# Relay_Control.net
KiCad netlist of a schematic drawn in EAGLE
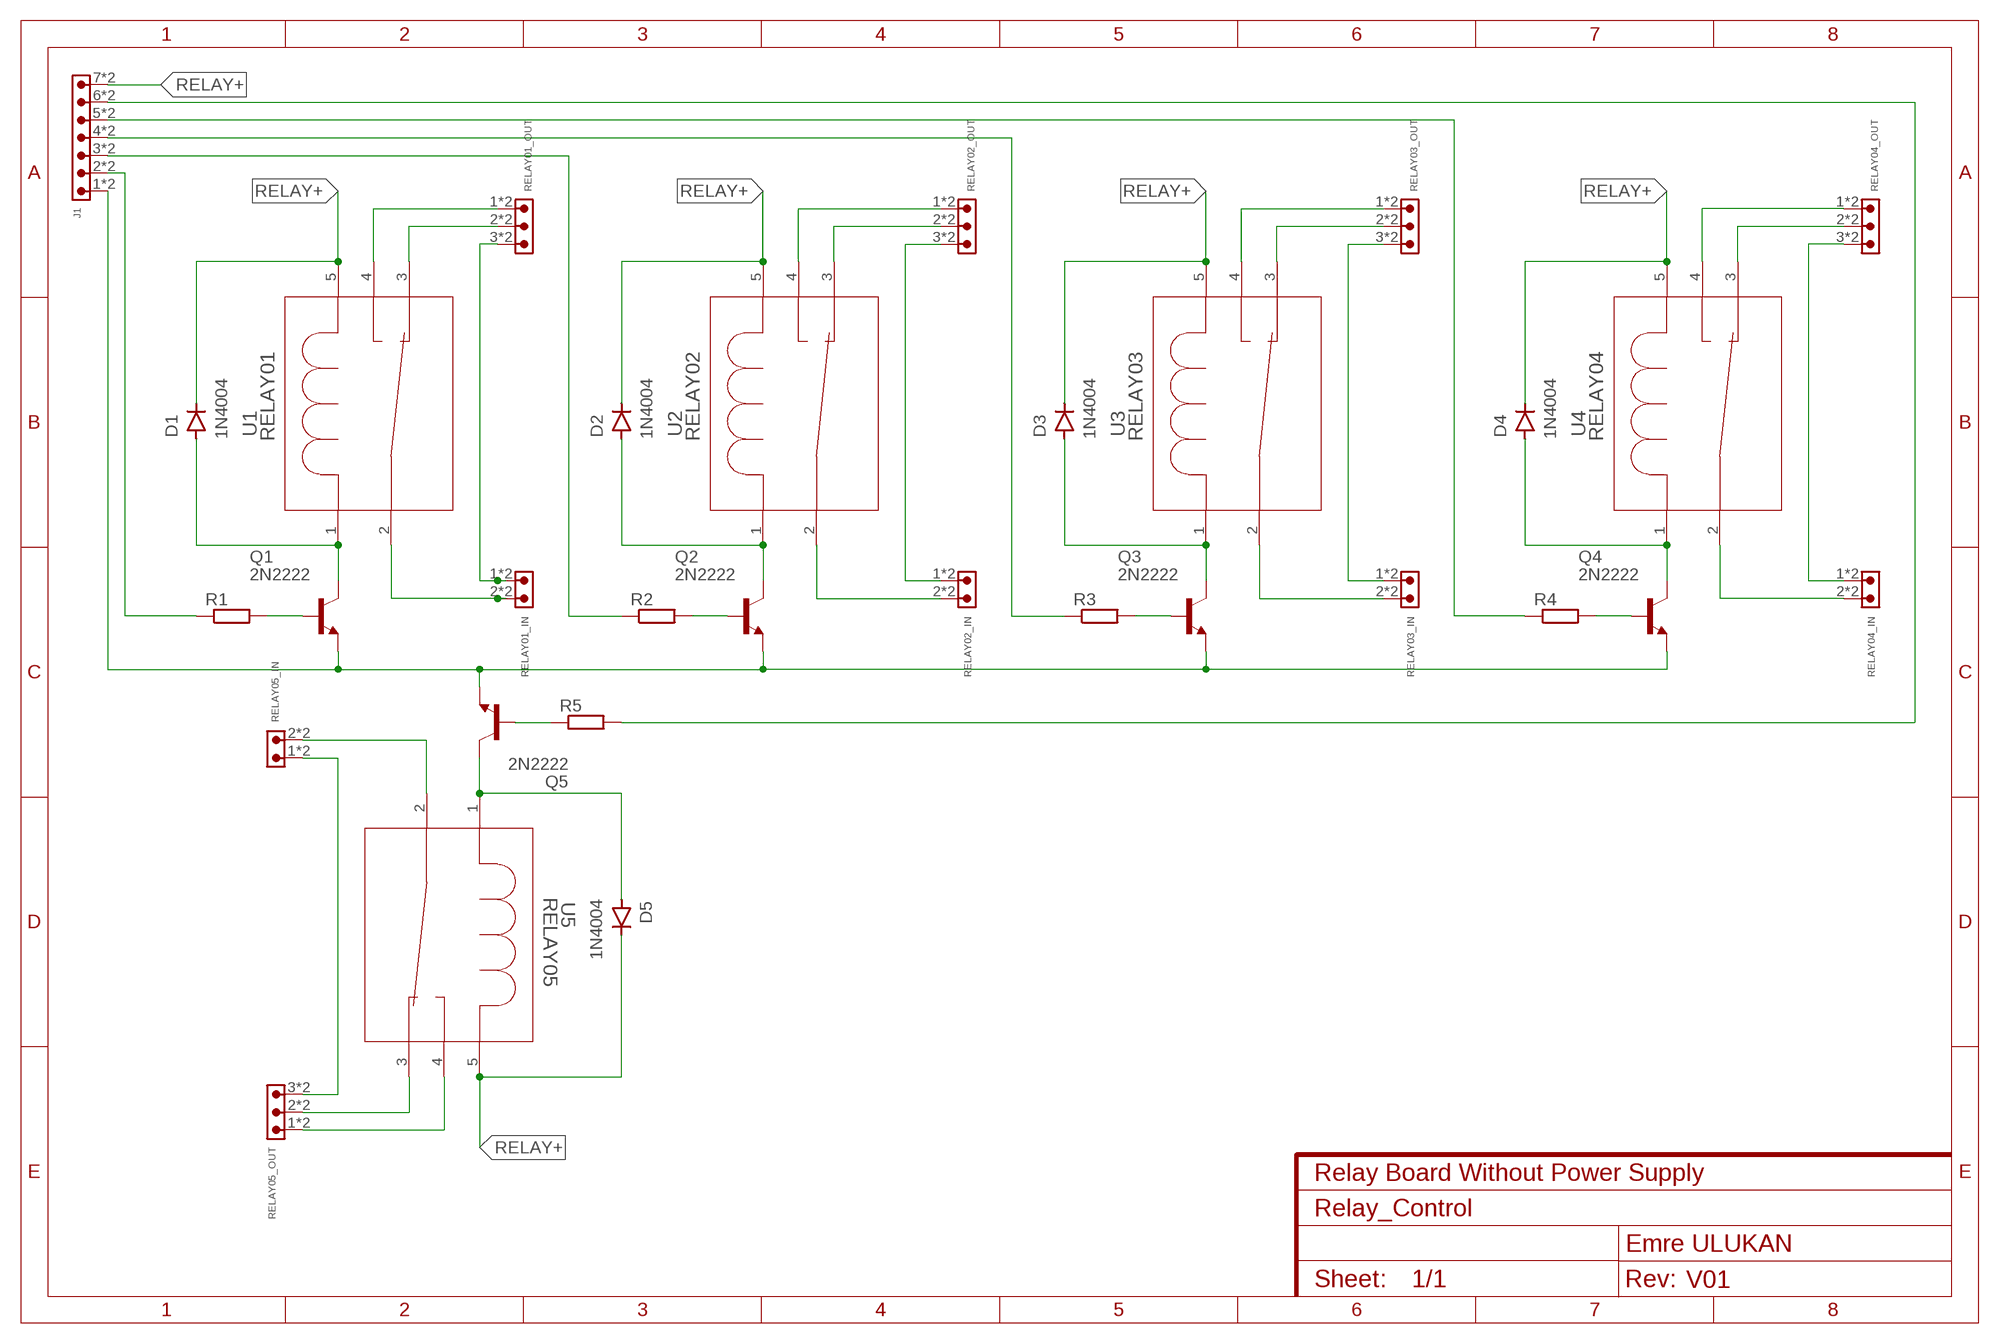
[diagram p0: schematic, sheet 1]

(export (version "E")
  (design (tool "Eeschema 10.0.6"))
  (components
    (comp (ref "D1")
      (value "1N4004")
      (footprint "eagle-import:DO-41")
      (fields
        (field (name "DIGIKEY_PART_NUMBER") "1N4004MSCT-ND")
        (field (name "MANUFACTURER") "Micro Commercial Co")
        (field (name "CREATED_BY") "PCBLayout.com")
      )
      (libsource (lib "eagle-import") (part "1N4004"))
    )
    (comp (ref "D2")
      (value "1N4004")
      (footprint "eagle-import:DO-41")
      (fields
        (field (name "DIGIKEY_PART_NUMBER") "1N4004MSCT-ND")
        (field (name "MANUFACTURER") "Micro Commercial Co")
        (field (name "CREATED_BY") "PCBLayout.com")
      )
      (libsource (lib "eagle-import") (part "1N4004"))
    )
    (comp (ref "D3")
      (value "1N4004")
      (footprint "eagle-import:DO-41")
      (fields
        (field (name "DIGIKEY_PART_NUMBER") "1N4004MSCT-ND")
        (field (name "MANUFACTURER") "Micro Commercial Co")
        (field (name "CREATED_BY") "PCBLayout.com")
      )
      (libsource (lib "eagle-import") (part "1N4004"))
    )
    (comp (ref "D4")
      (value "1N4004")
      (footprint "eagle-import:DO-41")
      (fields
        (field (name "DIGIKEY_PART_NUMBER") "1N4004MSCT-ND")
        (field (name "MANUFACTURER") "Micro Commercial Co")
        (field (name "CREATED_BY") "PCBLayout.com")
      )
      (libsource (lib "eagle-import") (part "1N4004"))
    )
    (comp (ref "D5")
      (value "1N4004")
      (footprint "eagle-import:DO-41")
      (fields
        (field (name "DIGIKEY_PART_NUMBER") "1N4004MSCT-ND")
        (field (name "MANUFACTURER") "Micro Commercial Co")
        (field (name "CREATED_BY") "PCBLayout.com")
      )
      (libsource (lib "eagle-import") (part "1N4004"))
    )
    (comp (ref "J1")
      (value "638263222007")
      (footprint "eagle-import:638263222007")
      (libsource (lib "eagle-import") (part "638263222007"))
    )
    (comp (ref "Q1")
      (value "2N2222")
      (footprint "eagle-import:TO18")
      (libsource (lib "eagle-import") (part "2N2222"))
    )
    (comp (ref "Q2")
      (value "2N2222")
      (footprint "eagle-import:TO18")
      (libsource (lib "eagle-import") (part "2N2222"))
    )
    (comp (ref "Q3")
      (value "2N2222")
      (footprint "eagle-import:TO18")
      (libsource (lib "eagle-import") (part "2N2222"))
    )
    (comp (ref "Q4")
      (value "2N2222")
      (footprint "eagle-import:TO18")
      (libsource (lib "eagle-import") (part "2N2222"))
    )
    (comp (ref "Q5")
      (value "2N2222")
      (footprint "eagle-import:TO18")
      (libsource (lib "eagle-import") (part "2N2222"))
    )
    (comp (ref "R1")
      (value "R-EU_0207/10")
      (footprint "eagle-import:0207_10")
      (libsource (lib "eagle-import") (part "R-EU_0207/10"))
    )
    (comp (ref "R2")
      (value "R-EU_0207/10")
      (footprint "eagle-import:0207_10")
      (libsource (lib "eagle-import") (part "R-EU_0207/10"))
    )
    (comp (ref "R3")
      (value "R-EU_0207/10")
      (footprint "eagle-import:0207_10")
      (libsource (lib "eagle-import") (part "R-EU_0207/10"))
    )
    (comp (ref "R4")
      (value "R-EU_0207/10")
      (footprint "eagle-import:0207_10")
      (libsource (lib "eagle-import") (part "R-EU_0207/10"))
    )
    (comp (ref "R5")
      (value "R-EU_0207/10")
      (footprint "eagle-import:0207_10")
      (libsource (lib "eagle-import") (part "R-EU_0207/10"))
    )
    (comp (ref "RELAY01_IN")
      (value "638263222002")
      (footprint "eagle-import:638263222002")
      (libsource (lib "eagle-import") (part "638263222002"))
    )
    (comp (ref "RELAY01_OUT")
      (value "638263222003")
      (footprint "eagle-import:638263222003")
      (libsource (lib "eagle-import") (part "638263222003"))
    )
    (comp (ref "RELAY02_IN")
      (value "638263222002")
      (footprint "eagle-import:638263222002")
      (libsource (lib "eagle-import") (part "638263222002"))
    )
    (comp (ref "RELAY02_OUT")
      (value "638263222003")
      (footprint "eagle-import:638263222003")
      (libsource (lib "eagle-import") (part "638263222003"))
    )
    (comp (ref "RELAY03_IN")
      (value "638263222002")
      (footprint "eagle-import:638263222002")
      (libsource (lib "eagle-import") (part "638263222002"))
    )
    (comp (ref "RELAY03_OUT")
      (value "638263222003")
      (footprint "eagle-import:638263222003")
      (libsource (lib "eagle-import") (part "638263222003"))
    )
    (comp (ref "RELAY04_IN")
      (value "638263222002")
      (footprint "eagle-import:638263222002")
      (libsource (lib "eagle-import") (part "638263222002"))
    )
    (comp (ref "RELAY04_OUT")
      (value "638263222003")
      (footprint "eagle-import:638263222003")
      (libsource (lib "eagle-import") (part "638263222003"))
    )
    (comp (ref "RELAY05_IN")
      (value "638263222002")
      (footprint "eagle-import:638263222002")
      (libsource (lib "eagle-import") (part "638263222002"))
    )
    (comp (ref "RELAY05_OUT")
      (value "638263222003")
      (footprint "eagle-import:638263222003")
      (libsource (lib "eagle-import") (part "638263222003"))
    )
    (comp (ref "U1")
      (value "RELAY01")
      (footprint "eagle-import:RELAY-SPDT_3.2MM")
      (fields
        (field (name "MANUFACTURER_PART_NUMBER") "RY211012")
        (field (name "COPYRIGHT") "Copyright (C) 2016 Accelerated Designs. All rights reserved")
      )
      (libsource (lib "eagle-import") (part "4-1393224-6"))
    )
    (comp (ref "U2")
      (value "RELAY02")
      (footprint "eagle-import:RELAY-SPDT_3.2MM")
      (fields
        (field (name "MANUFACTURER_PART_NUMBER") "RY211012")
        (field (name "COPYRIGHT") "Copyright (C) 2016 Accelerated Designs. All rights reserved")
      )
      (libsource (lib "eagle-import") (part "4-1393224-6"))
    )
    (comp (ref "U3")
      (value "RELAY03")
      (footprint "eagle-import:RELAY-SPDT_3.2MM")
      (fields
        (field (name "MANUFACTURER_PART_NUMBER") "RY211012")
        (field (name "COPYRIGHT") "Copyright (C) 2016 Accelerated Designs. All rights reserved")
      )
      (libsource (lib "eagle-import") (part "4-1393224-6"))
    )
    (comp (ref "U4")
      (value "RELAY04")
      (footprint "eagle-import:RELAY-SPDT_3.2MM")
      (fields
        (field (name "MANUFACTURER_PART_NUMBER") "RY211012")
        (field (name "COPYRIGHT") "Copyright (C) 2016 Accelerated Designs. All rights reserved")
      )
      (libsource (lib "eagle-import") (part "4-1393224-6"))
    )
    (comp (ref "U5")
      (value "RELAY05")
      (footprint "eagle-import:RELAY-SPDT_3.2MM")
      (fields
        (field (name "MANUFACTURER_PART_NUMBER") "RY211012")
        (field (name "COPYRIGHT") "Copyright (C) 2016 Accelerated Designs. All rights reserved")
      )
      (libsource (lib "eagle-import") (part "4-1393224-6"))
    )
  )
  (nets
    (net (code "1") (name "Net-(J1-2-PadA2)") (class "Default")
      (node (ref "J1") (pin "2") (pinfunction "2_2") (pintype "passive"))
      (node (ref "J1") (pin "A2") (pinfunction "2_A2") (pintype "passive"))
      (node (ref "R1") (pin "1") (pinfunction "1_1") (pintype "passive"))
    )
    (net (code "2") (name "Net-(J1-3-PadA3)") (class "Default")
      (node (ref "J1") (pin "3") (pinfunction "3_3") (pintype "passive"))
      (node (ref "J1") (pin "A3") (pinfunction "3_A3") (pintype "passive"))
      (node (ref "R2") (pin "1") (pinfunction "1_1") (pintype "passive"))
    )
    (net (code "3") (name "Net-(J1-4-PadA4)") (class "Default")
      (node (ref "J1") (pin "4") (pinfunction "4_4") (pintype "passive"))
      (node (ref "J1") (pin "A4") (pinfunction "4_A4") (pintype "passive"))
      (node (ref "R3") (pin "1") (pinfunction "1_1") (pintype "passive"))
    )
    (net (code "4") (name "Net-(J1-5-PadA5)") (class "Default")
      (node (ref "J1") (pin "5") (pinfunction "5_5") (pintype "passive"))
      (node (ref "J1") (pin "A5") (pinfunction "5_A5") (pintype "passive"))
      (node (ref "R4") (pin "1") (pinfunction "1_1") (pintype "passive"))
    )
    (net (code "5") (name "Net-(J1-6-PadA6)") (class "Default")
      (node (ref "J1") (pin "6") (pinfunction "6_6") (pintype "passive"))
      (node (ref "J1") (pin "A6") (pinfunction "6_A6") (pintype "passive"))
      (node (ref "R5") (pin "2") (pinfunction "2_2") (pintype "passive"))
    )
    (net (code "6") (name "Net-(Q1-B)") (class "Default")
      (node (ref "Q1") (pin "2") (pinfunction "B_2") (pintype "passive"))
      (node (ref "R1") (pin "2") (pinfunction "2_2") (pintype "passive"))
    )
    (net (code "7") (name "Net-(Q1-C)") (class "Default")
      (node (ref "D1") (pin "A") (pinfunction "A_A") (pintype "passive"))
      (node (ref "Q1") (pin "3") (pinfunction "C_3") (pintype "passive"))
      (node (ref "U1") (pin "1") (pinfunction "1_1") (pintype "passive"))
    )
    (net (code "8") (name "Net-(Q1-E)") (class "Default")
      (node (ref "J1") (pin "1") (pinfunction "1_1") (pintype "passive"))
      (node (ref "J1") (pin "A1") (pinfunction "1_A1") (pintype "passive"))
      (node (ref "Q1") (pin "1") (pinfunction "E_1") (pintype "passive"))
      (node (ref "Q2") (pin "1") (pinfunction "E_1") (pintype "passive"))
      (node (ref "Q3") (pin "1") (pinfunction "E_1") (pintype "passive"))
      (node (ref "Q4") (pin "1") (pinfunction "E_1") (pintype "passive"))
      (node (ref "Q5") (pin "1") (pinfunction "E_1") (pintype "passive"))
    )
    (net (code "9") (name "Net-(Q2-B)") (class "Default")
      (node (ref "Q2") (pin "2") (pinfunction "B_2") (pintype "passive"))
      (node (ref "R2") (pin "2") (pinfunction "2_2") (pintype "passive"))
    )
    (net (code "10") (name "Net-(Q2-C)") (class "Default")
      (node (ref "D2") (pin "A") (pinfunction "A_A") (pintype "passive"))
      (node (ref "Q2") (pin "3") (pinfunction "C_3") (pintype "passive"))
      (node (ref "U2") (pin "1") (pinfunction "1_1") (pintype "passive"))
    )
    (net (code "11") (name "Net-(Q3-B)") (class "Default")
      (node (ref "Q3") (pin "2") (pinfunction "B_2") (pintype "passive"))
      (node (ref "R3") (pin "2") (pinfunction "2_2") (pintype "passive"))
    )
    (net (code "12") (name "Net-(Q3-C)") (class "Default")
      (node (ref "D3") (pin "A") (pinfunction "A_A") (pintype "passive"))
      (node (ref "Q3") (pin "3") (pinfunction "C_3") (pintype "passive"))
      (node (ref "U3") (pin "1") (pinfunction "1_1") (pintype "passive"))
    )
    (net (code "13") (name "Net-(Q4-B)") (class "Default")
      (node (ref "Q4") (pin "2") (pinfunction "B_2") (pintype "passive"))
      (node (ref "R4") (pin "2") (pinfunction "2_2") (pintype "passive"))
    )
    (net (code "14") (name "Net-(Q4-C)") (class "Default")
      (node (ref "D4") (pin "A") (pinfunction "A_A") (pintype "passive"))
      (node (ref "Q4") (pin "3") (pinfunction "C_3") (pintype "passive"))
      (node (ref "U4") (pin "1") (pinfunction "1_1") (pintype "passive"))
    )
    (net (code "15") (name "Net-(Q5-B)") (class "Default")
      (node (ref "Q5") (pin "2") (pinfunction "B_2") (pintype "passive"))
      (node (ref "R5") (pin "1") (pinfunction "1_1") (pintype "passive"))
    )
    (net (code "16") (name "Net-(Q5-C)") (class "Default")
      (node (ref "D5") (pin "A") (pinfunction "A_A") (pintype "passive"))
      (node (ref "Q5") (pin "3") (pinfunction "C_3") (pintype "passive"))
      (node (ref "U5") (pin "1") (pinfunction "1_1") (pintype "passive"))
    )
    (net (code "17") (name "Net-(RELAY01_IN-1-PadA1)") (class "Default")
      (node (ref "RELAY01_IN") (pin "1") (pinfunction "1_1") (pintype "passive"))
      (node (ref "RELAY01_IN") (pin "A1") (pinfunction "1_A1") (pintype "passive"))
      (node (ref "RELAY01_OUT") (pin "3") (pinfunction "3_3") (pintype "passive"))
      (node (ref "RELAY01_OUT") (pin "A3") (pinfunction "3_A3") (pintype "passive"))
    )
    (net (code "18") (name "Net-(RELAY01_IN-2-PadA2)") (class "Default")
      (node (ref "RELAY01_IN") (pin "2") (pinfunction "2_2") (pintype "passive"))
      (node (ref "RELAY01_IN") (pin "A2") (pinfunction "2_A2") (pintype "passive"))
      (node (ref "U1") (pin "2") (pinfunction "2_2") (pintype "passive"))
    )
    (net (code "19") (name "Net-(RELAY01_OUT-1-PadA1)") (class "Default")
      (node (ref "RELAY01_OUT") (pin "1") (pinfunction "1_1") (pintype "passive"))
      (node (ref "RELAY01_OUT") (pin "A1") (pinfunction "1_A1") (pintype "passive"))
      (node (ref "U1") (pin "4") (pinfunction "4_4") (pintype "passive"))
    )
    (net (code "20") (name "Net-(RELAY01_OUT-2-PadA2)") (class "Default")
      (node (ref "RELAY01_OUT") (pin "2") (pinfunction "2_2") (pintype "passive"))
      (node (ref "RELAY01_OUT") (pin "A2") (pinfunction "2_A2") (pintype "passive"))
      (node (ref "U1") (pin "3") (pinfunction "3_3") (pintype "passive"))
    )
    (net (code "21") (name "Net-(RELAY02_IN-1-PadA1)") (class "Default")
      (node (ref "RELAY02_IN") (pin "1") (pinfunction "1_1") (pintype "passive"))
      (node (ref "RELAY02_IN") (pin "A1") (pinfunction "1_A1") (pintype "passive"))
      (node (ref "RELAY02_OUT") (pin "3") (pinfunction "3_3") (pintype "passive"))
      (node (ref "RELAY02_OUT") (pin "A3") (pinfunction "3_A3") (pintype "passive"))
    )
    (net (code "22") (name "Net-(RELAY02_IN-2-PadA2)") (class "Default")
      (node (ref "RELAY02_IN") (pin "2") (pinfunction "2_2") (pintype "passive"))
      (node (ref "RELAY02_IN") (pin "A2") (pinfunction "2_A2") (pintype "passive"))
      (node (ref "U2") (pin "2") (pinfunction "2_2") (pintype "passive"))
    )
    (net (code "23") (name "Net-(RELAY02_OUT-1-PadA1)") (class "Default")
      (node (ref "RELAY02_OUT") (pin "1") (pinfunction "1_1") (pintype "passive"))
      (node (ref "RELAY02_OUT") (pin "A1") (pinfunction "1_A1") (pintype "passive"))
      (node (ref "U2") (pin "4") (pinfunction "4_4") (pintype "passive"))
    )
    (net (code "24") (name "Net-(RELAY02_OUT-2-PadA2)") (class "Default")
      (node (ref "RELAY02_OUT") (pin "2") (pinfunction "2_2") (pintype "passive"))
      (node (ref "RELAY02_OUT") (pin "A2") (pinfunction "2_A2") (pintype "passive"))
      (node (ref "U2") (pin "3") (pinfunction "3_3") (pintype "passive"))
    )
    (net (code "25") (name "Net-(RELAY03_IN-1-PadA1)") (class "Default")
      (node (ref "RELAY03_IN") (pin "1") (pinfunction "1_1") (pintype "passive"))
      (node (ref "RELAY03_IN") (pin "A1") (pinfunction "1_A1") (pintype "passive"))
      (node (ref "RELAY03_OUT") (pin "3") (pinfunction "3_3") (pintype "passive"))
      (node (ref "RELAY03_OUT") (pin "A3") (pinfunction "3_A3") (pintype "passive"))
    )
    (net (code "26") (name "Net-(RELAY03_IN-2-PadA2)") (class "Default")
      (node (ref "RELAY03_IN") (pin "2") (pinfunction "2_2") (pintype "passive"))
      (node (ref "RELAY03_IN") (pin "A2") (pinfunction "2_A2") (pintype "passive"))
      (node (ref "U3") (pin "2") (pinfunction "2_2") (pintype "passive"))
    )
    (net (code "27") (name "Net-(RELAY03_OUT-1-PadA1)") (class "Default")
      (node (ref "RELAY03_OUT") (pin "1") (pinfunction "1_1") (pintype "passive"))
      (node (ref "RELAY03_OUT") (pin "A1") (pinfunction "1_A1") (pintype "passive"))
      (node (ref "U3") (pin "4") (pinfunction "4_4") (pintype "passive"))
    )
    (net (code "28") (name "Net-(RELAY03_OUT-2-PadA2)") (class "Default")
      (node (ref "RELAY03_OUT") (pin "2") (pinfunction "2_2") (pintype "passive"))
      (node (ref "RELAY03_OUT") (pin "A2") (pinfunction "2_A2") (pintype "passive"))
      (node (ref "U3") (pin "3") (pinfunction "3_3") (pintype "passive"))
    )
    (net (code "29") (name "Net-(RELAY04_IN-1-PadA1)") (class "Default")
      (node (ref "RELAY04_IN") (pin "1") (pinfunction "1_1") (pintype "passive"))
      (node (ref "RELAY04_IN") (pin "A1") (pinfunction "1_A1") (pintype "passive"))
      (node (ref "RELAY04_OUT") (pin "3") (pinfunction "3_3") (pintype "passive"))
      (node (ref "RELAY04_OUT") (pin "A3") (pinfunction "3_A3") (pintype "passive"))
    )
    (net (code "30") (name "Net-(RELAY04_IN-2-PadA2)") (class "Default")
      (node (ref "RELAY04_IN") (pin "2") (pinfunction "2_2") (pintype "passive"))
      (node (ref "RELAY04_IN") (pin "A2") (pinfunction "2_A2") (pintype "passive"))
      (node (ref "U4") (pin "2") (pinfunction "2_2") (pintype "passive"))
    )
    (net (code "31") (name "Net-(RELAY04_OUT-1-PadA1)") (class "Default")
      (node (ref "RELAY04_OUT") (pin "1") (pinfunction "1_1") (pintype "passive"))
      (node (ref "RELAY04_OUT") (pin "A1") (pinfunction "1_A1") (pintype "passive"))
      (node (ref "U4") (pin "4") (pinfunction "4_4") (pintype "passive"))
    )
    (net (code "32") (name "Net-(RELAY04_OUT-2-PadA2)") (class "Default")
      (node (ref "RELAY04_OUT") (pin "2") (pinfunction "2_2") (pintype "passive"))
      (node (ref "RELAY04_OUT") (pin "A2") (pinfunction "2_A2") (pintype "passive"))
      (node (ref "U4") (pin "3") (pinfunction "3_3") (pintype "passive"))
    )
    (net (code "33") (name "Net-(RELAY05_IN-1-PadA1)") (class "Default")
      (node (ref "RELAY05_IN") (pin "1") (pinfunction "1_1") (pintype "passive"))
      (node (ref "RELAY05_IN") (pin "A1") (pinfunction "1_A1") (pintype "passive"))
      (node (ref "RELAY05_OUT") (pin "3") (pinfunction "3_3") (pintype "passive"))
      (node (ref "RELAY05_OUT") (pin "A3") (pinfunction "3_A3") (pintype "passive"))
    )
    (net (code "34") (name "Net-(RELAY05_IN-2-PadA2)") (class "Default")
      (node (ref "RELAY05_IN") (pin "2") (pinfunction "2_2") (pintype "passive"))
      (node (ref "RELAY05_IN") (pin "A2") (pinfunction "2_A2") (pintype "passive"))
      (node (ref "U5") (pin "2") (pinfunction "2_2") (pintype "passive"))
    )
    (net (code "35") (name "Net-(RELAY05_OUT-1-PadA1)") (class "Default")
      (node (ref "RELAY05_OUT") (pin "1") (pinfunction "1_1") (pintype "passive"))
      (node (ref "RELAY05_OUT") (pin "A1") (pinfunction "1_A1") (pintype "passive"))
      (node (ref "U5") (pin "4") (pinfunction "4_4") (pintype "passive"))
    )
    (net (code "36") (name "Net-(RELAY05_OUT-2-PadA2)") (class "Default")
      (node (ref "RELAY05_OUT") (pin "2") (pinfunction "2_2") (pintype "passive"))
      (node (ref "RELAY05_OUT") (pin "A2") (pinfunction "2_A2") (pintype "passive"))
      (node (ref "U5") (pin "3") (pinfunction "3_3") (pintype "passive"))
    )
    (net (code "37") (name "RELAY+") (class "Default")
      (node (ref "D1") (pin "C") (pinfunction "C_C") (pintype "passive"))
      (node (ref "D2") (pin "C") (pinfunction "C_C") (pintype "passive"))
      (node (ref "D3") (pin "C") (pinfunction "C_C") (pintype "passive"))
      (node (ref "D4") (pin "C") (pinfunction "C_C") (pintype "passive"))
      (node (ref "D5") (pin "C") (pinfunction "C_C") (pintype "passive"))
      (node (ref "J1") (pin "7") (pinfunction "7_7") (pintype "passive"))
      (node (ref "J1") (pin "A7") (pinfunction "7_A7") (pintype "passive"))
      (node (ref "U1") (pin "5") (pinfunction "5_5") (pintype "passive"))
      (node (ref "U2") (pin "5") (pinfunction "5_5") (pintype "passive"))
      (node (ref "U3") (pin "5") (pinfunction "5_5") (pintype "passive"))
      (node (ref "U4") (pin "5") (pinfunction "5_5") (pintype "passive"))
      (node (ref "U5") (pin "5") (pinfunction "5_5") (pintype "passive"))
    )
  )
)
